# Display_de_vidas_y_nivel.net
KiCad netlist of a schematic drawn in EAGLE
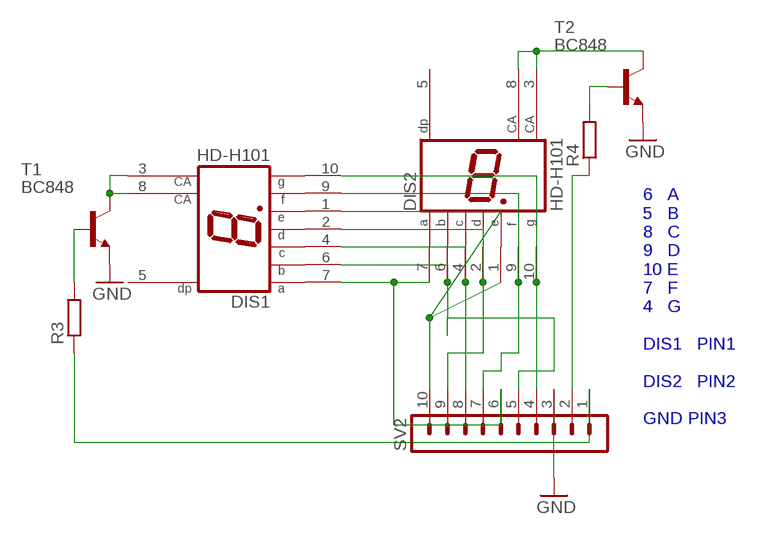
[diagram p0: schematic, sheet 1]

(export (version "E")
  (design (tool "Eeschema 10.0.6"))
  (components
    (comp (ref "DIS1")
      (value "HD-H101")
      (footprint "eagle-import:HDSP-M")
      (libsource (lib "eagle-import") (part "HD-H101"))
    )
    (comp (ref "DIS2")
      (value "HD-H101")
      (footprint "eagle-import:HDSP-M")
      (libsource (lib "eagle-import") (part "HD-H101"))
    )
    (comp (ref "R3")
      (value "R-EU_M0805")
      (footprint "eagle-import:M0805")
      (libsource (lib "eagle-import") (part "R-EU_M0805"))
    )
    (comp (ref "R4")
      (value "R-EU_M0805")
      (footprint "eagle-import:M0805")
      (libsource (lib "eagle-import") (part "R-EU_M0805"))
    )
    (comp (ref "SV2")
      (value "MA10-1")
      (footprint "eagle-import:MA10-1")
      (libsource (lib "eagle-import") (part "MA10-1"))
    )
    (comp (ref "T1")
      (value "BC848")
      (footprint "eagle-import:SOT23")
      (libsource (lib "eagle-import") (part "BC848"))
    )
    (comp (ref "T2")
      (value "BC848")
      (footprint "eagle-import:SOT23")
      (libsource (lib "eagle-import") (part "BC848"))
    )
  )
  (nets
    (net (code "1") (name "GND") (class "Default")
      (node (ref "SV2") (pin "3") (pinfunction "3_3") (pintype "passive"))
      (node (ref "T1") (pin "2") (pinfunction "E_2") (pintype "passive"))
      (node (ref "T2") (pin "2") (pinfunction "E_2") (pintype "passive"))
    )
    (net (code "2") (name "Net-(DIS1-A)") (class "Default")
      (node (ref "DIS1") (pin "7") (pinfunction "A_7") (pintype "passive"))
      (node (ref "DIS2") (pin "7") (pinfunction "A_7") (pintype "passive"))
      (node (ref "SV2") (pin "6") (pinfunction "6_6") (pintype "passive"))
    )
    (net (code "3") (name "Net-(DIS1-B)") (class "Default")
      (node (ref "DIS1") (pin "6") (pinfunction "B_6") (pintype "passive"))
      (node (ref "DIS2") (pin "6") (pinfunction "B_6") (pintype "passive"))
      (node (ref "SV2") (pin "5") (pinfunction "5_5") (pintype "passive"))
    )
    (net (code "4") (name "Net-(DIS1-C)") (class "Default")
      (node (ref "DIS1") (pin "4") (pinfunction "C_4") (pintype "passive"))
      (node (ref "DIS2") (pin "4") (pinfunction "C_4") (pintype "passive"))
      (node (ref "SV2") (pin "8") (pinfunction "8_8") (pintype "passive"))
    )
    (net (code "5") (name "Net-(DIS1-D)") (class "Default")
      (node (ref "DIS1") (pin "2") (pinfunction "D_2") (pintype "passive"))
      (node (ref "DIS2") (pin "2") (pinfunction "D_2") (pintype "passive"))
      (node (ref "SV2") (pin "9") (pinfunction "9_9") (pintype "passive"))
    )
    (net (code "6") (name "Net-(DIS1-E)") (class "Default")
      (node (ref "DIS1") (pin "1") (pinfunction "E_1") (pintype "passive"))
      (node (ref "DIS2") (pin "1") (pinfunction "E_1") (pintype "passive"))
      (node (ref "SV2") (pin "10") (pinfunction "10_10") (pintype "passive"))
    )
    (net (code "7") (name "Net-(DIS1-F)") (class "Default")
      (node (ref "DIS1") (pin "9") (pinfunction "F_9") (pintype "passive"))
      (node (ref "DIS2") (pin "9") (pinfunction "F_9") (pintype "passive"))
      (node (ref "SV2") (pin "7") (pinfunction "7_7") (pintype "passive"))
    )
    (net (code "8") (name "Net-(DIS1-G)") (class "Default")
      (node (ref "DIS1") (pin "10") (pinfunction "G_10") (pintype "passive"))
      (node (ref "DIS2") (pin "10") (pinfunction "G_10") (pintype "passive"))
      (node (ref "SV2") (pin "4") (pinfunction "4_4") (pintype "passive"))
    )
    (net (code "9") (name "Net-(R3-Pad1)") (class "Default")
      (node (ref "R3") (pin "1") (pinfunction "1_1") (pintype "passive"))
      (node (ref "SV2") (pin "1") (pinfunction "1_1") (pintype "passive"))
    )
    (net (code "10") (name "Net-(R4-Pad1)") (class "Default")
      (node (ref "R4") (pin "1") (pinfunction "1_1") (pintype "passive"))
      (node (ref "SV2") (pin "2") (pinfunction "2_2") (pintype "passive"))
    )
    (net (code "11") (name "Net-(T1-B)") (class "Default")
      (node (ref "R3") (pin "2") (pinfunction "2_2") (pintype "passive"))
      (node (ref "T1") (pin "1") (pinfunction "B_1") (pintype "passive"))
    )
    (net (code "12") (name "Net-(T1-C)") (class "Default")
      (node (ref "DIS1") (pin "3") (pinfunction "CA_3") (pintype "passive"))
      (node (ref "DIS1") (pin "8") (pinfunction "CA_8") (pintype "passive"))
      (node (ref "T1") (pin "3") (pinfunction "C_3") (pintype "passive"))
    )
    (net (code "13") (name "Net-(T2-B)") (class "Default")
      (node (ref "R4") (pin "2") (pinfunction "2_2") (pintype "passive"))
      (node (ref "T2") (pin "1") (pinfunction "B_1") (pintype "passive"))
    )
    (net (code "14") (name "Net-(T2-C)") (class "Default")
      (node (ref "DIS2") (pin "3") (pinfunction "CA_3") (pintype "passive"))
      (node (ref "DIS2") (pin "8") (pinfunction "CA_8") (pintype "passive"))
      (node (ref "T2") (pin "3") (pinfunction "C_3") (pintype "passive"))
    )
    (net (code "15") (name "unconnected-(DIS1-DP-Pad5)") (class "Default")
      (node (ref "DIS1") (pin "5") (pinfunction "DP_5") (pintype "passive"))
    )
    (net (code "16") (name "unconnected-(DIS2-DP-Pad5)") (class "Default")
      (node (ref "DIS2") (pin "5") (pinfunction "DP_5") (pintype "passive"))
    )
  )
)
